# SNAC_7ch_SMS_DB9_3D_in_Housing_with_JST.net
KiCad netlist of a schematic drawn in EAGLE
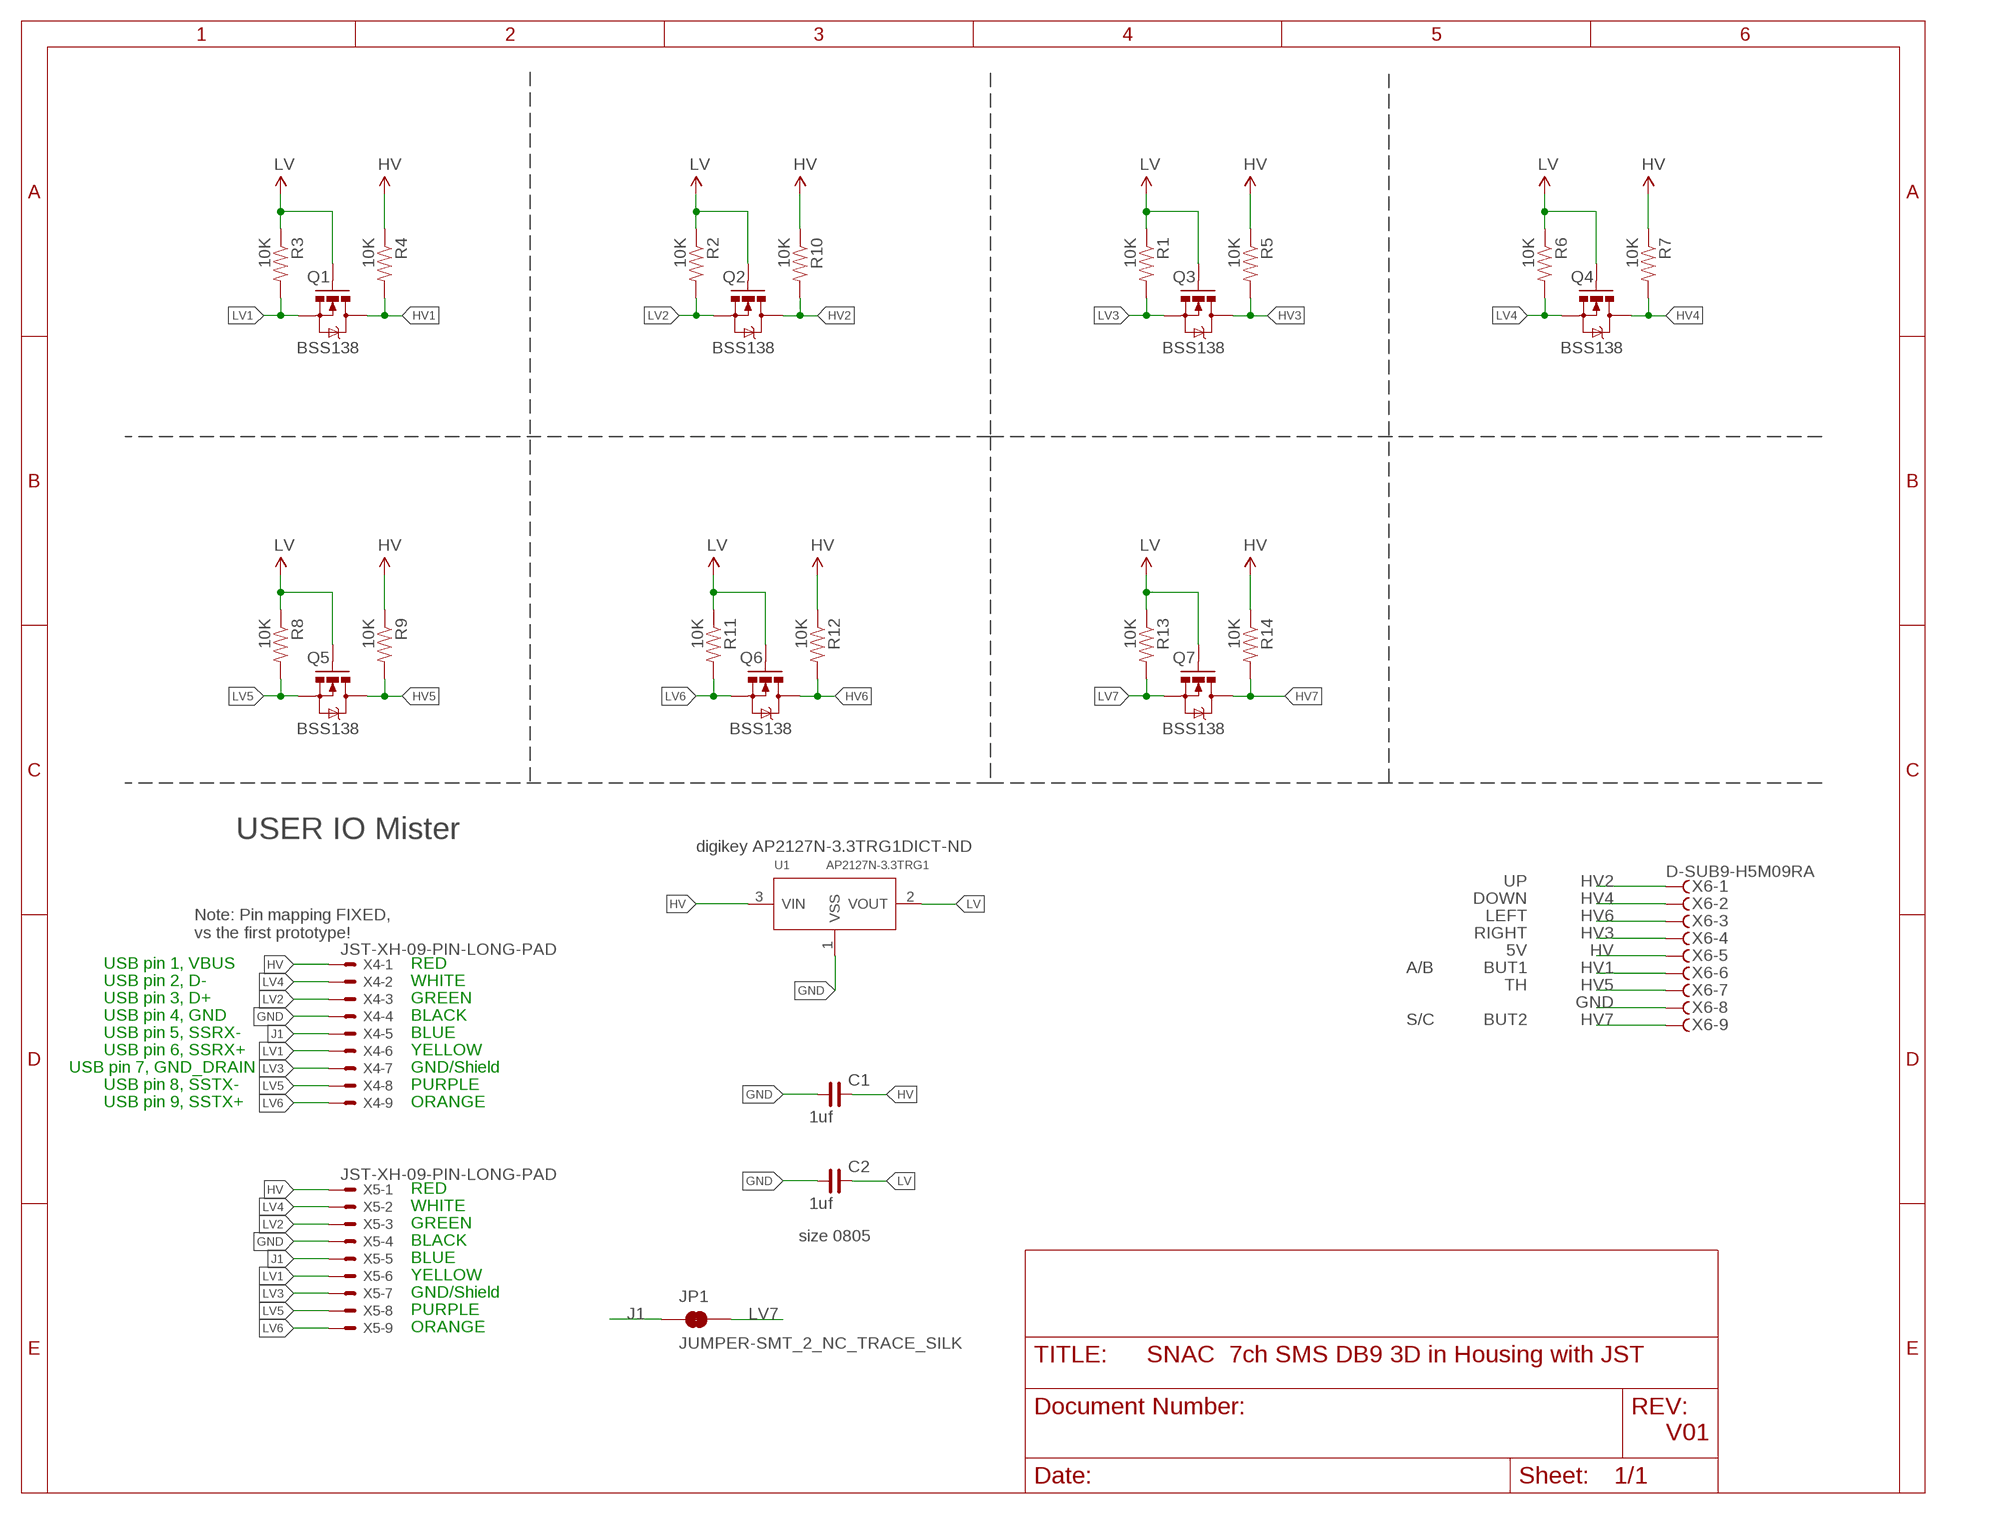
[diagram p0: schematic, sheet 1, part 1 of 2]
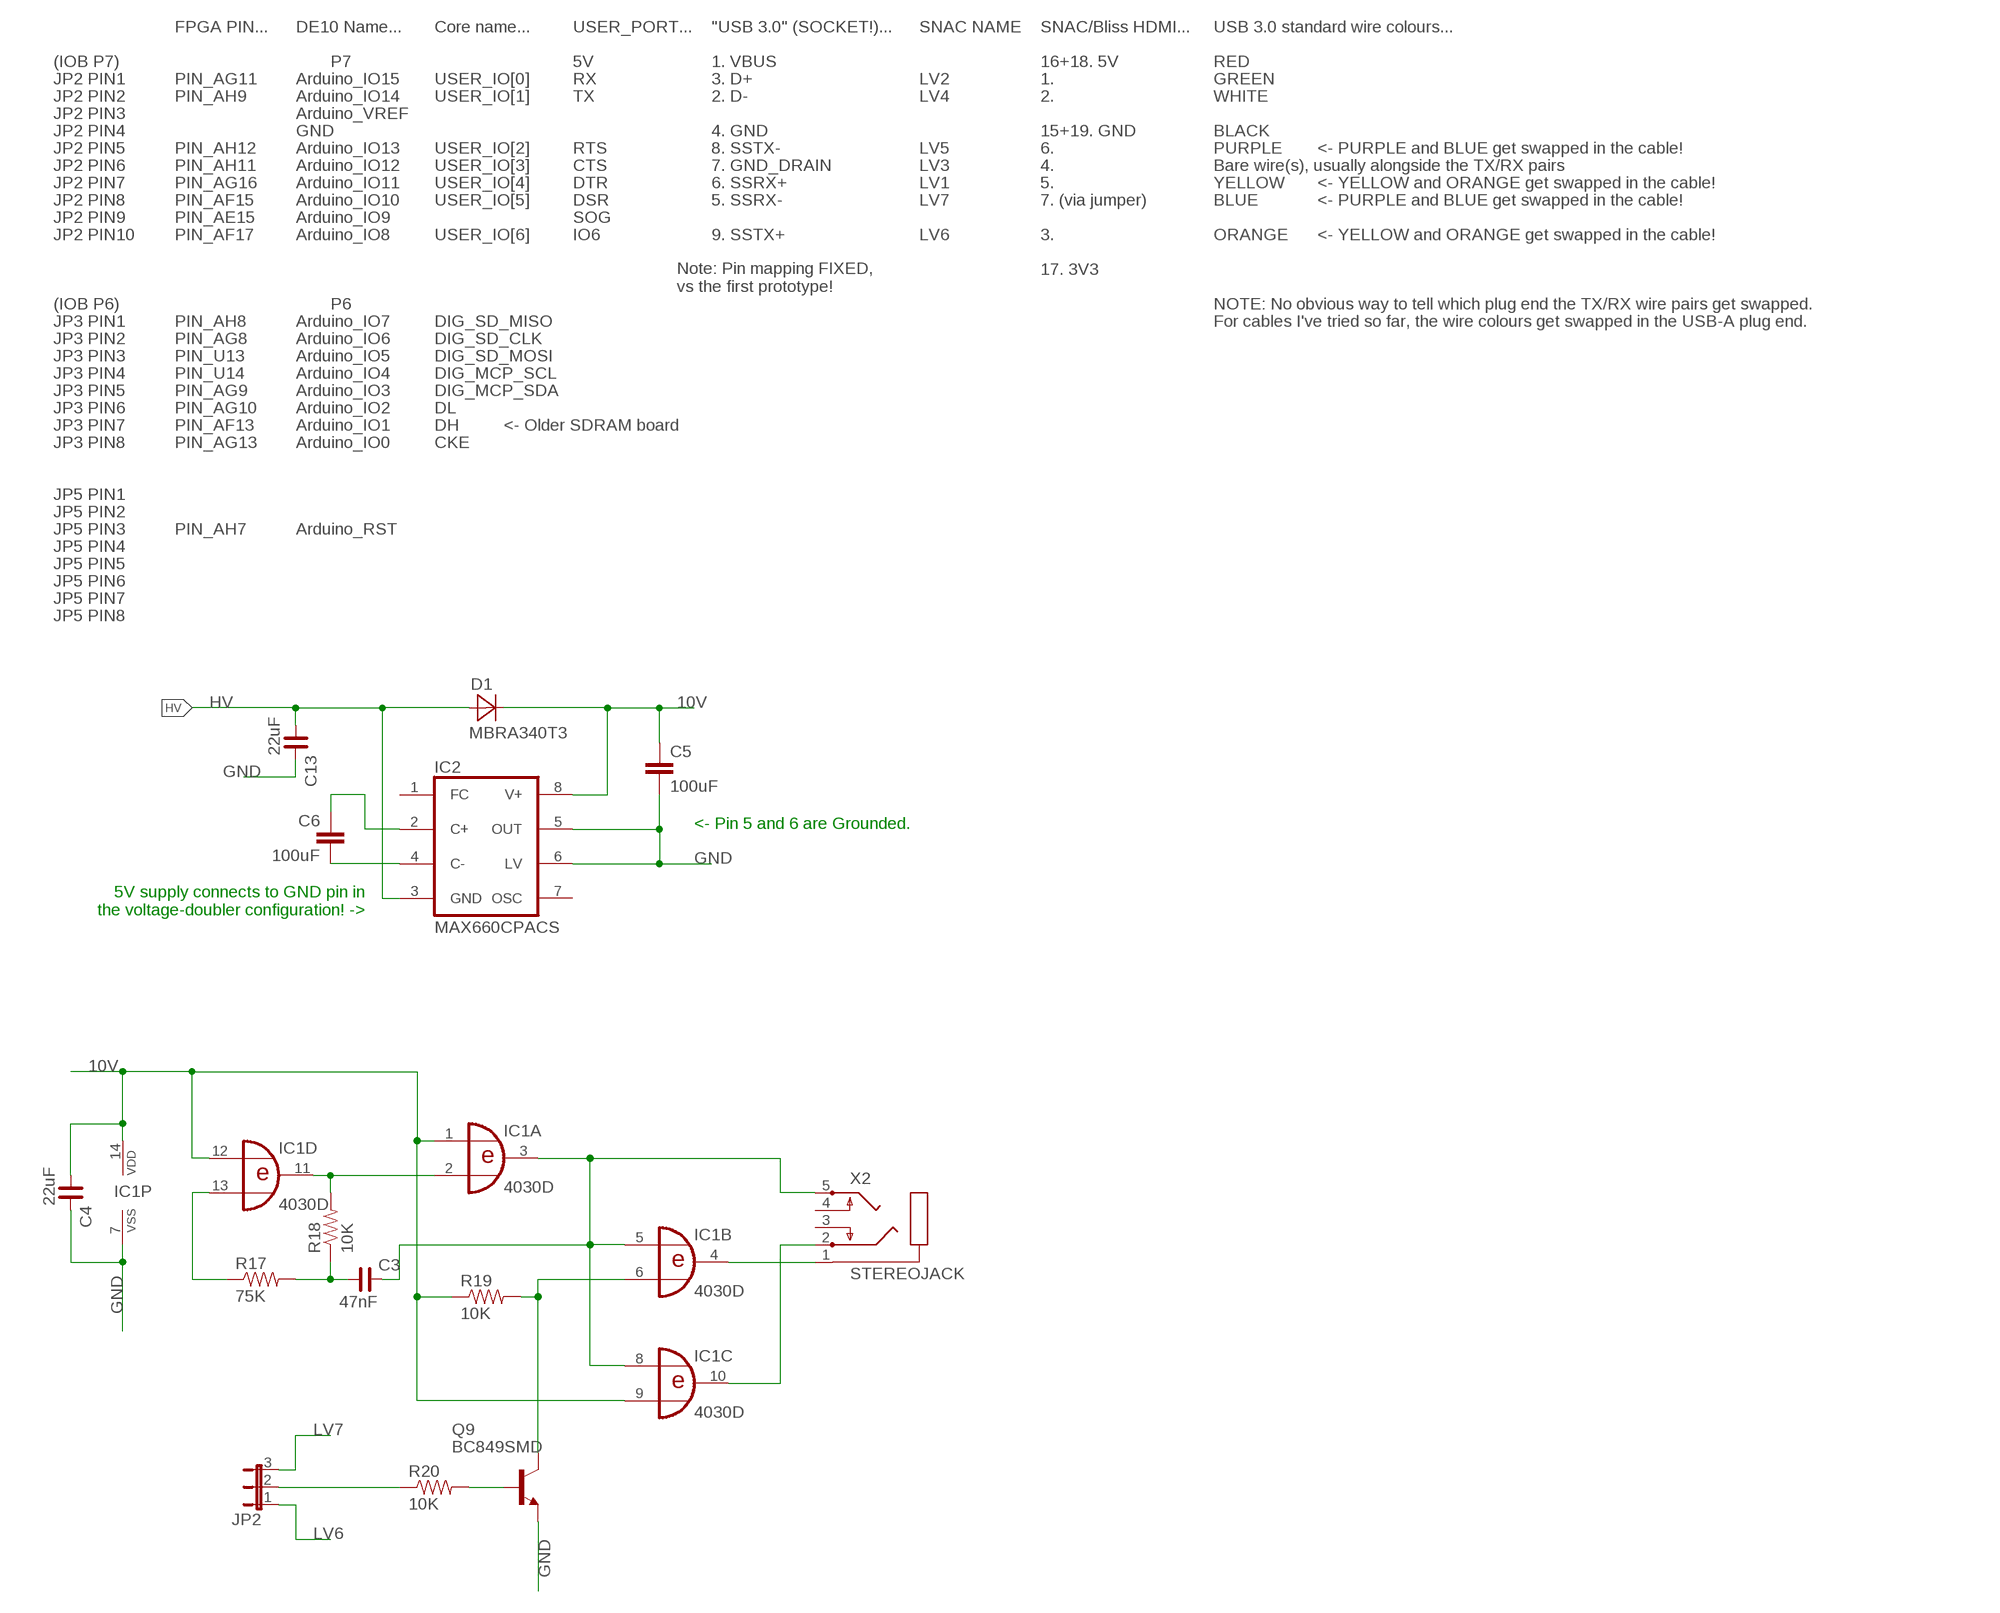
[diagram p1: schematic, sheet 1, part 2 of 2]

(export (version "E")
  (design (tool "Eeschema 10.0.6"))
  (components
    (comp (ref "C1")
      (value "1uf")
      (footprint "eagle-import:C0805")
      (libsource (lib "eagle-import") (part "C_0805"))
    )
    (comp (ref "C2")
      (value "1uf")
      (footprint "eagle-import:C0805")
      (libsource (lib "eagle-import") (part "C_0805"))
    )
    (comp (ref "C3")
      (value "47nF")
      (footprint "eagle-import:C0805")
      (libsource (lib "eagle-import") (part "C_0805"))
    )
    (comp (ref "C4")
      (value "22uF")
      (footprint "eagle-import:C0805")
      (libsource (lib "eagle-import") (part "C_0805"))
    )
    (comp (ref "C5")
      (value "100uF")
      (footprint "eagle-import:C1812")
      (libsource (lib "eagle-import") (part "C-EUC1812"))
    )
    (comp (ref "C6")
      (value "100uF")
      (footprint "eagle-import:C1812")
      (libsource (lib "eagle-import") (part "C-EUC1812"))
    )
    (comp (ref "C13")
      (value "22uF")
      (footprint "eagle-import:C0805")
      (libsource (lib "eagle-import") (part "C_0805"))
    )
    (comp (ref "D1")
      (value "MBRA340T3")
      (footprint "eagle-import:SMA")
      (libsource (lib "eagle-import") (part "MBRA340T3"))
    )
    (comp (ref "IC1")
      (value "4030D")
      (footprint "eagle-import:SO14")
      (libsource (lib "eagle-import") (part "4030D"))
    )
    (comp (ref "IC2")
      (value "MAX660CPACS")
      (footprint "eagle-import:SO08")
      (libsource (lib "eagle-import") (part "MAX660CPACS"))
    )
    (comp (ref "JP1")
      (value "JUMPER-SMT_2_NC_TRACE_SILK")
      (footprint "eagle-import:SMT-JUMPER_2_NC_TRACE_SILK")
      (libsource (lib "eagle-import") (part "JUMPER-SMT_2_NC_TRACE_SILK"))
    )
    (comp (ref "JP2")
      (value "JP2E")
      (footprint "eagle-import:JP2")
      (libsource (lib "eagle-import") (part "JP2E"))
    )
    (comp (ref "Q1")
      (value "BSS138")
      (footprint "eagle-import:SOT23-3")
      (libsource (lib "eagle-import") (part "MOSFET-NCHANNELSMD"))
    )
    (comp (ref "Q2")
      (value "BSS138")
      (footprint "eagle-import:SOT23-3")
      (libsource (lib "eagle-import") (part "MOSFET-NCHANNELSMD"))
    )
    (comp (ref "Q3")
      (value "BSS138")
      (footprint "eagle-import:SOT23-3")
      (libsource (lib "eagle-import") (part "MOSFET-NCHANNELSMD"))
    )
    (comp (ref "Q4")
      (value "BSS138")
      (footprint "eagle-import:SOT23-3")
      (libsource (lib "eagle-import") (part "MOSFET-NCHANNELSMD"))
    )
    (comp (ref "Q5")
      (value "BSS138")
      (footprint "eagle-import:SOT23-3")
      (libsource (lib "eagle-import") (part "MOSFET-NCHANNELSMD"))
    )
    (comp (ref "Q6")
      (value "BSS138")
      (footprint "eagle-import:SOT23-3")
      (libsource (lib "eagle-import") (part "MOSFET-NCHANNELSMD"))
    )
    (comp (ref "Q7")
      (value "BSS138")
      (footprint "eagle-import:SOT23-3")
      (libsource (lib "eagle-import") (part "MOSFET-NCHANNELSMD"))
    )
    (comp (ref "Q9")
      (value "BC849SMD")
      (footprint "eagle-import:SOT23-BEC")
      (libsource (lib "eagle-import") (part "BC849SMD"))
    )
    (comp (ref "R1")
      (value "10K")
      (footprint "eagle-import:0603-RES")
      (libsource (lib "eagle-import") (part "RESISTOR0603-RES"))
    )
    (comp (ref "R2")
      (value "10K")
      (footprint "eagle-import:0603-RES")
      (libsource (lib "eagle-import") (part "RESISTOR0603-RES"))
    )
    (comp (ref "R3")
      (value "10K")
      (footprint "eagle-import:0603-RES")
      (libsource (lib "eagle-import") (part "RESISTOR0603-RES"))
    )
    (comp (ref "R4")
      (value "10K")
      (footprint "eagle-import:0603-RES")
      (libsource (lib "eagle-import") (part "RESISTOR0603-RES"))
    )
    (comp (ref "R5")
      (value "10K")
      (footprint "eagle-import:0603-RES")
      (libsource (lib "eagle-import") (part "RESISTOR0603-RES"))
    )
    (comp (ref "R6")
      (value "10K")
      (footprint "eagle-import:0603-RES")
      (libsource (lib "eagle-import") (part "RESISTOR0603-RES"))
    )
    (comp (ref "R7")
      (value "10K")
      (footprint "eagle-import:0603-RES")
      (libsource (lib "eagle-import") (part "RESISTOR0603-RES"))
    )
    (comp (ref "R8")
      (value "10K")
      (footprint "eagle-import:0603-RES")
      (libsource (lib "eagle-import") (part "RESISTOR0603-RES"))
    )
    (comp (ref "R9")
      (value "10K")
      (footprint "eagle-import:0603-RES")
      (libsource (lib "eagle-import") (part "RESISTOR0603-RES"))
    )
    (comp (ref "R10")
      (value "10K")
      (footprint "eagle-import:0603-RES")
      (libsource (lib "eagle-import") (part "RESISTOR0603-RES"))
    )
    (comp (ref "R11")
      (value "10K")
      (footprint "eagle-import:0603-RES")
      (libsource (lib "eagle-import") (part "RESISTOR0603-RES"))
    )
    (comp (ref "R12")
      (value "10K")
      (footprint "eagle-import:0603-RES")
      (libsource (lib "eagle-import") (part "RESISTOR0603-RES"))
    )
    (comp (ref "R13")
      (value "10K")
      (footprint "eagle-import:0603-RES")
      (libsource (lib "eagle-import") (part "RESISTOR0603-RES"))
    )
    (comp (ref "R14")
      (value "10K")
      (footprint "eagle-import:0603-RES")
      (libsource (lib "eagle-import") (part "RESISTOR0603-RES"))
    )
    (comp (ref "R17")
      (value "75K")
      (footprint "eagle-import:0603-RES")
      (libsource (lib "eagle-import") (part "RESISTOR0603-RES"))
    )
    (comp (ref "R18")
      (value "10K")
      (footprint "eagle-import:0603-RES")
      (libsource (lib "eagle-import") (part "RESISTOR0603-RES"))
    )
    (comp (ref "R19")
      (value "10K")
      (footprint "eagle-import:0603-RES")
      (libsource (lib "eagle-import") (part "RESISTOR0603-RES"))
    )
    (comp (ref "R20")
      (value "10K")
      (footprint "eagle-import:0603-RES")
      (libsource (lib "eagle-import") (part "RESISTOR0603-RES"))
    )
    (comp (ref "U1")
      (value "AP2127N-3.3TRG1")
      (footprint "eagle-import:SOT-23")
      (fields (field (name "MF") "Torex") (field (name "MP") "XC6206P332MR-G"))
      (libsource (lib "eagle-import") (part "PMIC-LDO-XC6206P332MR-G(SOT23)"))
    )
    (comp (ref "X2")
      (value "STEREOJACK")
      (footprint "eagle-import:STX3100")
      (libsource (lib "eagle-import") (part "STEREOJACK"))
    )
    (comp (ref "X4")
      (value "JST-XH-09-PIN-LONG-PAD")
      (footprint "eagle-import:JST-XH-09-PACKAGE-LONG-PAD")
      (libsource (lib "eagle-import") (part "JST-XH-09-PIN-LONG-PAD"))
    )
    (comp (ref "X5")
      (value "JST-XH-09-PIN-LONG-PAD")
      (footprint "eagle-import:JST-XH-09-PACKAGE-LONG-PAD")
      (libsource (lib "eagle-import") (part "JST-XH-09-PIN-LONG-PAD"))
    )
    (comp (ref "X6")
      (value "D-SUB9-H5M09RA")
      (footprint "eagle-import:H5M09RA")
      (libsource (lib "eagle-import") (part "D-SUB9-H5M09RA"))
    )
  )
  (nets
    (net (code "1") (name "/10V") (class "Default")
      (node (ref "C4") (pin "1") (pinfunction "1_1") (pintype "passive"))
      (node (ref "C5") (pin "1") (pinfunction "1_1") (pintype "passive"))
      (node (ref "D1") (pin "C") (pinfunction "C_C") (pintype "passive"))
      (node (ref "IC1") (pin "1") (pinfunction "I0_1") (pintype "input"))
      (node (ref "IC1") (pin "12") (pinfunction "I0_12") (pintype "input"))
      (node (ref "IC1") (pin "14") (pinfunction "VDD_14") (pintype "power_in"))
      (node (ref "IC1") (pin "9") (pinfunction "I1_9") (pintype "input"))
      (node (ref "IC2") (pin "8") (pinfunction "V+_8") (pintype "power_in"))
      (node (ref "R19") (pin "1") (pinfunction "1_1") (pintype "passive"))
    )
    (net (code "2") (name "GND") (class "Default")
      (node (ref "C1") (pin "1") (pinfunction "1_1") (pintype "passive"))
      (node (ref "C13") (pin "2") (pinfunction "2_2") (pintype "passive"))
      (node (ref "C2") (pin "1") (pinfunction "1_1") (pintype "passive"))
      (node (ref "C4") (pin "2") (pinfunction "2_2") (pintype "passive"))
      (node (ref "C5") (pin "2") (pinfunction "2_2") (pintype "passive"))
      (node (ref "IC1") (pin "7") (pinfunction "VSS_7") (pintype "power_in"))
      (node (ref "IC2") (pin "5") (pinfunction "OUT_5") (pintype "power_in"))
      (node (ref "IC2") (pin "6") (pinfunction "LV_6") (pintype "passive"))
      (node (ref "Q9") (pin "E") (pinfunction "E_E") (pintype "passive"))
      (node (ref "U1") (pin "1") (pinfunction "VSS_1") (pintype "power_in"))
      (node (ref "X4") (pin "4") (pinfunction "S_4") (pintype "passive"))
      (node (ref "X5") (pin "4") (pinfunction "S_4") (pintype "passive"))
      (node (ref "X6") (pin "8") (pinfunction "F_8") (pintype "passive"))
    )
    (net (code "3") (name "HV") (class "Default")
      (node (ref "C1") (pin "2") (pinfunction "2_2") (pintype "passive"))
      (node (ref "C13") (pin "1") (pinfunction "1_1") (pintype "passive"))
      (node (ref "D1") (pin "A") (pinfunction "A_A") (pintype "passive"))
      (node (ref "IC2") (pin "3") (pinfunction "GND_3") (pintype "power_in"))
      (node (ref "R10") (pin "1") (pinfunction "1_1") (pintype "passive"))
      (node (ref "R12") (pin "1") (pinfunction "1_1") (pintype "passive"))
      (node (ref "R14") (pin "1") (pinfunction "1_1") (pintype "passive"))
      (node (ref "R4") (pin "1") (pinfunction "1_1") (pintype "passive"))
      (node (ref "R5") (pin "1") (pinfunction "1_1") (pintype "passive"))
      (node (ref "R7") (pin "1") (pinfunction "1_1") (pintype "passive"))
      (node (ref "R9") (pin "1") (pinfunction "1_1") (pintype "passive"))
      (node (ref "U1") (pin "3") (pinfunction "VIN_3") (pintype "input"))
      (node (ref "X4") (pin "1") (pinfunction "S_1") (pintype "passive"))
      (node (ref "X5") (pin "1") (pinfunction "S_1") (pintype "passive"))
      (node (ref "X6") (pin "5") (pinfunction "F_5") (pintype "passive"))
    )
    (net (code "4") (name "HV1") (class "Default")
      (node (ref "Q1") (pin "3") (pinfunction "D_3") (pintype "passive"))
      (node (ref "R4") (pin "2") (pinfunction "2_2") (pintype "passive"))
      (node (ref "X6") (pin "6") (pinfunction "F_6") (pintype "passive"))
    )
    (net (code "5") (name "HV2") (class "Default")
      (node (ref "Q2") (pin "3") (pinfunction "D_3") (pintype "passive"))
      (node (ref "R10") (pin "2") (pinfunction "2_2") (pintype "passive"))
      (node (ref "X6") (pin "1") (pinfunction "F_1") (pintype "passive"))
    )
    (net (code "6") (name "HV3") (class "Default")
      (node (ref "Q3") (pin "3") (pinfunction "D_3") (pintype "passive"))
      (node (ref "R5") (pin "2") (pinfunction "2_2") (pintype "passive"))
      (node (ref "X6") (pin "4") (pinfunction "F_4") (pintype "passive"))
    )
    (net (code "7") (name "HV4") (class "Default")
      (node (ref "Q4") (pin "3") (pinfunction "D_3") (pintype "passive"))
      (node (ref "R7") (pin "2") (pinfunction "2_2") (pintype "passive"))
      (node (ref "X6") (pin "2") (pinfunction "F_2") (pintype "passive"))
    )
    (net (code "8") (name "HV5") (class "Default")
      (node (ref "Q5") (pin "3") (pinfunction "D_3") (pintype "passive"))
      (node (ref "R9") (pin "2") (pinfunction "2_2") (pintype "passive"))
      (node (ref "X6") (pin "7") (pinfunction "F_7") (pintype "passive"))
    )
    (net (code "9") (name "HV6") (class "Default")
      (node (ref "Q6") (pin "3") (pinfunction "D_3") (pintype "passive"))
      (node (ref "R12") (pin "2") (pinfunction "2_2") (pintype "passive"))
      (node (ref "X6") (pin "3") (pinfunction "F_3") (pintype "passive"))
    )
    (net (code "10") (name "HV7") (class "Default")
      (node (ref "Q7") (pin "3") (pinfunction "D_3") (pintype "passive"))
      (node (ref "R14") (pin "2") (pinfunction "2_2") (pintype "passive"))
      (node (ref "X6") (pin "9") (pinfunction "F_9") (pintype "passive"))
    )
    (net (code "11") (name "J1") (class "Default")
      (node (ref "JP1") (pin "1") (pinfunction "1_1") (pintype "passive"))
      (node (ref "X4") (pin "5") (pinfunction "S_5") (pintype "passive"))
      (node (ref "X5") (pin "5") (pinfunction "S_5") (pintype "passive"))
    )
    (net (code "12") (name "LV") (class "Default")
      (node (ref "C2") (pin "2") (pinfunction "2_2") (pintype "passive"))
      (node (ref "Q1") (pin "1") (pinfunction "G_1") (pintype "passive"))
      (node (ref "Q2") (pin "1") (pinfunction "G_1") (pintype "passive"))
      (node (ref "Q3") (pin "1") (pinfunction "G_1") (pintype "passive"))
      (node (ref "Q4") (pin "1") (pinfunction "G_1") (pintype "passive"))
      (node (ref "Q5") (pin "1") (pinfunction "G_1") (pintype "passive"))
      (node (ref "Q6") (pin "1") (pinfunction "G_1") (pintype "passive"))
      (node (ref "Q7") (pin "1") (pinfunction "G_1") (pintype "passive"))
      (node (ref "R1") (pin "1") (pinfunction "1_1") (pintype "passive"))
      (node (ref "R11") (pin "1") (pinfunction "1_1") (pintype "passive"))
      (node (ref "R13") (pin "1") (pinfunction "1_1") (pintype "passive"))
      (node (ref "R2") (pin "1") (pinfunction "1_1") (pintype "passive"))
      (node (ref "R3") (pin "1") (pinfunction "1_1") (pintype "passive"))
      (node (ref "R6") (pin "1") (pinfunction "1_1") (pintype "passive"))
      (node (ref "R8") (pin "1") (pinfunction "1_1") (pintype "passive"))
      (node (ref "U1") (pin "2") (pinfunction "VOUT_2") (pintype "output"))
    )
    (net (code "13") (name "LV1") (class "Default")
      (node (ref "Q1") (pin "2") (pinfunction "S_2") (pintype "passive"))
      (node (ref "R3") (pin "2") (pinfunction "2_2") (pintype "passive"))
      (node (ref "X4") (pin "6") (pinfunction "S_6") (pintype "passive"))
      (node (ref "X5") (pin "6") (pinfunction "S_6") (pintype "passive"))
    )
    (net (code "14") (name "LV2") (class "Default")
      (node (ref "Q2") (pin "2") (pinfunction "S_2") (pintype "passive"))
      (node (ref "R2") (pin "2") (pinfunction "2_2") (pintype "passive"))
      (node (ref "X4") (pin "3") (pinfunction "S_3") (pintype "passive"))
      (node (ref "X5") (pin "3") (pinfunction "S_3") (pintype "passive"))
    )
    (net (code "15") (name "LV3") (class "Default")
      (node (ref "Q3") (pin "2") (pinfunction "S_2") (pintype "passive"))
      (node (ref "R1") (pin "2") (pinfunction "2_2") (pintype "passive"))
      (node (ref "X4") (pin "7") (pinfunction "S_7") (pintype "passive"))
      (node (ref "X5") (pin "7") (pinfunction "S_7") (pintype "passive"))
    )
    (net (code "16") (name "LV4") (class "Default")
      (node (ref "Q4") (pin "2") (pinfunction "S_2") (pintype "passive"))
      (node (ref "R6") (pin "2") (pinfunction "2_2") (pintype "passive"))
      (node (ref "X4") (pin "2") (pinfunction "S_2") (pintype "passive"))
      (node (ref "X5") (pin "2") (pinfunction "S_2") (pintype "passive"))
    )
    (net (code "17") (name "LV5") (class "Default")
      (node (ref "Q5") (pin "2") (pinfunction "S_2") (pintype "passive"))
      (node (ref "R8") (pin "2") (pinfunction "2_2") (pintype "passive"))
      (node (ref "X4") (pin "8") (pinfunction "S_8") (pintype "passive"))
      (node (ref "X5") (pin "8") (pinfunction "S_8") (pintype "passive"))
    )
    (net (code "18") (name "LV6") (class "Default")
      (node (ref "JP2") (pin "1") (pinfunction "1_1") (pintype "passive"))
      (node (ref "Q6") (pin "2") (pinfunction "S_2") (pintype "passive"))
      (node (ref "R11") (pin "2") (pinfunction "2_2") (pintype "passive"))
      (node (ref "X4") (pin "9") (pinfunction "S_9") (pintype "passive"))
      (node (ref "X5") (pin "9") (pinfunction "S_9") (pintype "passive"))
    )
    (net (code "19") (name "LV7") (class "Default")
      (node (ref "JP1") (pin "2") (pinfunction "2_2") (pintype "passive"))
      (node (ref "JP2") (pin "3") (pinfunction "3_3") (pintype "passive"))
      (node (ref "Q7") (pin "2") (pinfunction "S_2") (pintype "passive"))
      (node (ref "R13") (pin "2") (pinfunction "2_2") (pintype "passive"))
    )
    (net (code "20") (name "Net-(C3-Pad1)") (class "Default")
      (node (ref "C3") (pin "1") (pinfunction "1_1") (pintype "passive"))
      (node (ref "R17") (pin "2") (pinfunction "2_2") (pintype "passive"))
      (node (ref "R18") (pin "1") (pinfunction "1_1") (pintype "passive"))
    )
    (net (code "21") (name "Net-(IC1A-I1)") (class "Default")
      (node (ref "IC1") (pin "11") (pinfunction "O_11") (pintype "output"))
      (node (ref "IC1") (pin "2") (pinfunction "I1_2") (pintype "input"))
      (node (ref "R18") (pin "2") (pinfunction "2_2") (pintype "passive"))
    )
    (net (code "22") (name "Net-(IC1A-O)") (class "Default")
      (node (ref "C3") (pin "2") (pinfunction "2_2") (pintype "passive"))
      (node (ref "IC1") (pin "3") (pinfunction "O_3") (pintype "output"))
      (node (ref "IC1") (pin "5") (pinfunction "I0_5") (pintype "input"))
      (node (ref "IC1") (pin "8") (pinfunction "I0_8") (pintype "input"))
      (node (ref "X2") (pin "5") (pinfunction "5_5") (pintype "passive"))
    )
    (net (code "23") (name "Net-(IC1B-I1)") (class "Default")
      (node (ref "IC1") (pin "6") (pinfunction "I1_6") (pintype "input"))
      (node (ref "Q9") (pin "C") (pinfunction "C_C") (pintype "passive"))
      (node (ref "R19") (pin "2") (pinfunction "2_2") (pintype "passive"))
    )
    (net (code "24") (name "Net-(IC1B-O)") (class "Default")
      (node (ref "IC1") (pin "4") (pinfunction "O_4") (pintype "output"))
      (node (ref "X2") (pin "1") (pinfunction "1_1") (pintype "passive"))
    )
    (net (code "25") (name "Net-(IC1C-O)") (class "Default")
      (node (ref "IC1") (pin "10") (pinfunction "O_10") (pintype "output"))
      (node (ref "X2") (pin "2") (pinfunction "2_2") (pintype "passive"))
    )
    (net (code "26") (name "Net-(IC1D-I1)") (class "Default")
      (node (ref "IC1") (pin "13") (pinfunction "I1_13") (pintype "input"))
      (node (ref "R17") (pin "1") (pinfunction "1_1") (pintype "passive"))
    )
    (net (code "27") (name "Net-(IC2-C+)") (class "Default")
      (node (ref "C6") (pin "1") (pinfunction "1_1") (pintype "passive"))
      (node (ref "IC2") (pin "2") (pinfunction "C+_2") (pintype "passive"))
    )
    (net (code "28") (name "Net-(IC2-C-)") (class "Default")
      (node (ref "C6") (pin "2") (pinfunction "2_2") (pintype "passive"))
      (node (ref "IC2") (pin "4") (pinfunction "C-_4") (pintype "passive"))
    )
    (net (code "29") (name "Net-(JP2-Pad2)") (class "Default")
      (node (ref "JP2") (pin "2") (pinfunction "2_2") (pintype "passive"))
      (node (ref "R20") (pin "1") (pinfunction "1_1") (pintype "passive"))
    )
    (net (code "30") (name "Net-(Q9-PadB)") (class "Default")
      (node (ref "Q9") (pin "B") (pinfunction "B_B") (pintype "passive"))
      (node (ref "R20") (pin "2") (pinfunction "2_2") (pintype "passive"))
    )
    (net (code "31") (name "unconnected-(IC2-FC-Pad1)") (class "Default")
      (node (ref "IC2") (pin "1") (pinfunction "FC_1") (pintype "input"))
    )
    (net (code "32") (name "unconnected-(IC2-OSC-Pad7)") (class "Default")
      (node (ref "IC2") (pin "7") (pinfunction "OSC_7") (pintype "output"))
    )
    (net (code "33") (name "unconnected-(X2-Pad3)") (class "Default")
      (node (ref "X2") (pin "3") (pinfunction "3_3") (pintype "passive"))
    )
    (net (code "34") (name "unconnected-(X2-Pad4)") (class "Default")
      (node (ref "X2") (pin "4") (pinfunction "4_4") (pintype "passive"))
    )
  )
)
